# board.net
KiCad netlist of a schematic drawn in EAGLE
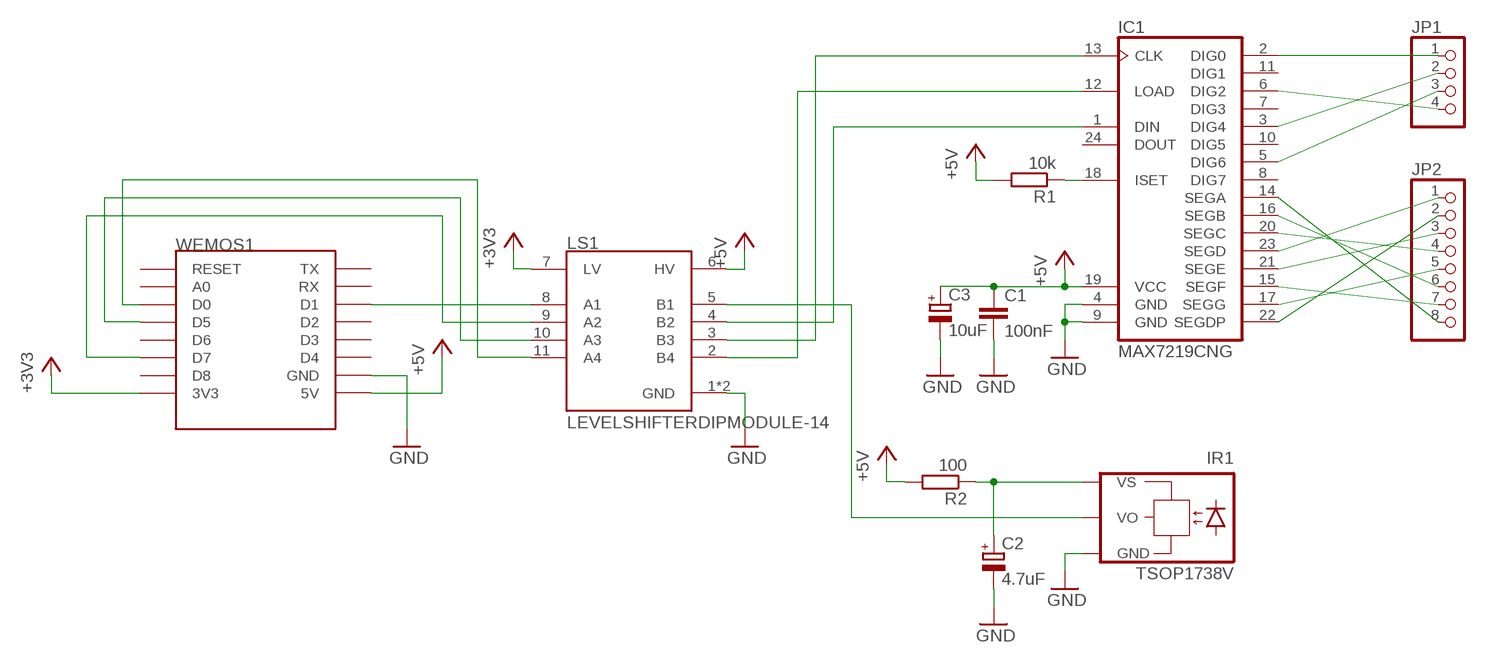
[diagram p0: schematic, sheet 1]

(export (version "E")
  (design (tool "Eeschema 10.0.6"))
  (components
    (comp (ref "C1")
      (value "100nF")
      (footprint "eagle-import:C050-024X044")
      (libsource (lib "eagle-import") (part "C-EU050-024X044"))
    )
    (comp (ref "C2")
      (value "4.7uF")
      (footprint "eagle-import:E1,8-4")
      (libsource (lib "eagle-import") (part "CPOL-EUE1.8-4"))
    )
    (comp (ref "C3")
      (value "10uF")
      (footprint "eagle-import:E1,8-4")
      (libsource (lib "eagle-import") (part "CPOL-EUE1.8-4"))
    )
    (comp (ref "IC1")
      (value "MAX7219CNG")
      (footprint "eagle-import:DIL24-3")
      (fields (field (name "MF") "MAXIM"))
      (libsource (lib "eagle-import") (part "MAX7219CNG"))
    )
    (comp (ref "IR1")
      (value "TSOP1738V")
      (footprint "eagle-import:TSOP17_V")
      (libsource (lib "eagle-import") (part "TSOP17V38"))
    )
    (comp (ref "JP1")
      (value "PINHD-1X4")
      (footprint "eagle-import:1X04")
      (libsource (lib "eagle-import") (part "PINHD-1X4"))
    )
    (comp (ref "JP2")
      (value "PINHD-1X8")
      (footprint "eagle-import:1X08")
      (libsource (lib "eagle-import") (part "PINHD-1X8"))
    )
    (comp (ref "LS1")
      (value "LEVELSHIFTERDIPMODULE-14")
      (footprint "eagle-import:DIP1016W53P254L1969H508Q12B")
      (libsource (lib "eagle-import") (part "LEVELSHIFTERDIPMODULE-14"))
    )
    (comp (ref "R1")
      (value "10k")
      (footprint "eagle-import:0207_10")
      (libsource (lib "eagle-import") (part "R-EU_0207/10"))
    )
    (comp (ref "R2")
      (value "100")
      (footprint "eagle-import:0207_10")
      (libsource (lib "eagle-import") (part "R-EU_0207/10"))
    )
    (comp (ref "WEMOS1")
      (value "WEMOS-D1-MINI")
      (footprint "eagle-import:WEMOS-D1-MINI")
      (libsource (lib "eagle-import") (part "WEMOS-D1-MINI"))
    )
  )
  (nets
    (net (code "1") (name "+3V3") (class "Default")
      (node (ref "LS1") (pin "7") (pinfunction "LV_7") (pintype "power_in"))
      (node (ref "WEMOS1") (pin "3V3") (pinfunction "3V3_3V3") (pintype "bidirectional"))
    )
    (net (code "2") (name "+5V") (class "Default")
      (node (ref "C1") (pin "1") (pinfunction "1_1") (pintype "passive"))
      (node (ref "C3") (pin "+") (pinfunction "+_+") (pintype "passive"))
      (node (ref "IC1") (pin "19") (pinfunction "VCC_19") (pintype "power_in"))
      (node (ref "LS1") (pin "6") (pinfunction "HV_6") (pintype "power_in"))
      (node (ref "R1") (pin "2") (pinfunction "2_2") (pintype "passive"))
      (node (ref "R2") (pin "2") (pinfunction "2_2") (pintype "passive"))
      (node (ref "WEMOS1") (pin "5V") (pinfunction "5V_5V") (pintype "bidirectional"))
    )
    (net (code "3") (name "GND") (class "Default")
      (node (ref "C1") (pin "2") (pinfunction "2_2") (pintype "passive"))
      (node (ref "C2") (pin "-") (pinfunction "-_-") (pintype "passive"))
      (node (ref "C3") (pin "-") (pinfunction "-_-") (pintype "passive"))
      (node (ref "IC1") (pin "4") (pinfunction "GND_4") (pintype "power_in"))
      (node (ref "IC1") (pin "9") (pinfunction "GND_9") (pintype "power_in"))
      (node (ref "IR1") (pin "GND") (pinfunction "GND_GND") (pintype "power_in"))
      (node (ref "LS1") (pin "1") (pinfunction "GND_1") (pintype "power_in"))
      (node (ref "LS1") (pin "12") (pinfunction "GND_12") (pintype "power_in"))
      (node (ref "WEMOS1") (pin "GND") (pinfunction "GND_GND") (pintype "bidirectional"))
    )
    (net (code "4") (name "Net-(C2-Pad+)") (class "Default")
      (node (ref "C2") (pin "+") (pinfunction "+_+") (pintype "passive"))
      (node (ref "IR1") (pin "VS") (pinfunction "VS_VS") (pintype "power_in"))
      (node (ref "R2") (pin "1") (pinfunction "1_1") (pintype "passive"))
    )
    (net (code "5") (name "Net-(IC1-CLK)") (class "Default")
      (node (ref "IC1") (pin "13") (pinfunction "CLK_13") (pintype "input"))
      (node (ref "LS1") (pin "3") (pinfunction "B3_3") (pintype "bidirectional"))
    )
    (net (code "6") (name "Net-(IC1-DIG0)") (class "Default")
      (node (ref "IC1") (pin "2") (pinfunction "DIG0_2") (pintype "output"))
      (node (ref "JP1") (pin "1") (pinfunction "1_1") (pintype "passive"))
    )
    (net (code "7") (name "Net-(IC1-DIG2)") (class "Default")
      (node (ref "IC1") (pin "6") (pinfunction "DIG2_6") (pintype "output"))
      (node (ref "JP1") (pin "4") (pinfunction "4_4") (pintype "passive"))
    )
    (net (code "8") (name "Net-(IC1-DIG4)") (class "Default")
      (node (ref "IC1") (pin "3") (pinfunction "DIG4_3") (pintype "output"))
      (node (ref "JP1") (pin "2") (pinfunction "2_2") (pintype "passive"))
    )
    (net (code "9") (name "Net-(IC1-DIG6)") (class "Default")
      (node (ref "IC1") (pin "5") (pinfunction "DIG6_5") (pintype "output"))
      (node (ref "JP1") (pin "3") (pinfunction "3_3") (pintype "passive"))
    )
    (net (code "10") (name "Net-(IC1-DIN)") (class "Default")
      (node (ref "IC1") (pin "1") (pinfunction "DIN_1") (pintype "input"))
      (node (ref "LS1") (pin "4") (pinfunction "B2_4") (pintype "bidirectional"))
    )
    (net (code "11") (name "Net-(IC1-ISET)") (class "Default")
      (node (ref "IC1") (pin "18") (pinfunction "ISET_18") (pintype "input"))
      (node (ref "R1") (pin "1") (pinfunction "1_1") (pintype "passive"))
    )
    (net (code "12") (name "Net-(IC1-LOAD)") (class "Default")
      (node (ref "IC1") (pin "12") (pinfunction "LOAD_12") (pintype "input"))
      (node (ref "LS1") (pin "2") (pinfunction "B4_2") (pintype "bidirectional"))
    )
    (net (code "13") (name "Net-(IC1-SEGA)") (class "Default")
      (node (ref "IC1") (pin "14") (pinfunction "SEGA_14") (pintype "output"))
      (node (ref "JP2") (pin "8") (pinfunction "8_8") (pintype "passive"))
    )
    (net (code "14") (name "Net-(IC1-SEGB)") (class "Default")
      (node (ref "IC1") (pin "16") (pinfunction "SEGB_16") (pintype "output"))
      (node (ref "JP2") (pin "6") (pinfunction "6_6") (pintype "passive"))
    )
    (net (code "15") (name "Net-(IC1-SEGC)") (class "Default")
      (node (ref "IC1") (pin "20") (pinfunction "SEGC_20") (pintype "output"))
      (node (ref "JP2") (pin "4") (pinfunction "4_4") (pintype "passive"))
    )
    (net (code "16") (name "Net-(IC1-SEGD)") (class "Default")
      (node (ref "IC1") (pin "23") (pinfunction "SEGD_23") (pintype "output"))
      (node (ref "JP2") (pin "1") (pinfunction "1_1") (pintype "passive"))
    )
    (net (code "17") (name "Net-(IC1-SEGDP)") (class "Default")
      (node (ref "IC1") (pin "22") (pinfunction "SEGDP_22") (pintype "output"))
      (node (ref "JP2") (pin "2") (pinfunction "2_2") (pintype "passive"))
    )
    (net (code "18") (name "Net-(IC1-SEGE)") (class "Default")
      (node (ref "IC1") (pin "21") (pinfunction "SEGE_21") (pintype "output"))
      (node (ref "JP2") (pin "3") (pinfunction "3_3") (pintype "passive"))
    )
    (net (code "19") (name "Net-(IC1-SEGF)") (class "Default")
      (node (ref "IC1") (pin "15") (pinfunction "SEGF_15") (pintype "output"))
      (node (ref "JP2") (pin "7") (pinfunction "7_7") (pintype "passive"))
    )
    (net (code "20") (name "Net-(IC1-SEGG)") (class "Default")
      (node (ref "IC1") (pin "17") (pinfunction "SEGG_17") (pintype "output"))
      (node (ref "JP2") (pin "5") (pinfunction "5_5") (pintype "passive"))
    )
    (net (code "21") (name "Net-(LS1-A1)") (class "Default")
      (node (ref "LS1") (pin "8") (pinfunction "A1_8") (pintype "bidirectional"))
      (node (ref "WEMOS1") (pin "D1") (pinfunction "D1_D1") (pintype "bidirectional"))
    )
    (net (code "22") (name "Net-(LS1-A2)") (class "Default")
      (node (ref "LS1") (pin "9") (pinfunction "A2_9") (pintype "bidirectional"))
      (node (ref "WEMOS1") (pin "D7") (pinfunction "D7_D7") (pintype "bidirectional"))
    )
    (net (code "23") (name "Net-(LS1-A3)") (class "Default")
      (node (ref "LS1") (pin "10") (pinfunction "A3_10") (pintype "bidirectional"))
      (node (ref "WEMOS1") (pin "D5") (pinfunction "D5_D5") (pintype "bidirectional"))
    )
    (net (code "24") (name "Net-(LS1-A4)") (class "Default")
      (node (ref "LS1") (pin "11") (pinfunction "A4_11") (pintype "bidirectional"))
      (node (ref "WEMOS1") (pin "D0") (pinfunction "D0_D0") (pintype "bidirectional"))
    )
    (net (code "25") (name "Net-(LS1-B1)") (class "Default")
      (node (ref "IR1") (pin "VO") (pinfunction "VO_VO") (pintype "open_collector"))
      (node (ref "LS1") (pin "5") (pinfunction "B1_5") (pintype "bidirectional"))
    )
    (net (code "26") (name "unconnected-(IC1-DIG1-Pad11)") (class "Default")
      (node (ref "IC1") (pin "11") (pinfunction "DIG1_11") (pintype "output"))
    )
    (net (code "27") (name "unconnected-(IC1-DIG3-Pad7)") (class "Default")
      (node (ref "IC1") (pin "7") (pinfunction "DIG3_7") (pintype "output"))
    )
    (net (code "28") (name "unconnected-(IC1-DIG5-Pad10)") (class "Default")
      (node (ref "IC1") (pin "10") (pinfunction "DIG5_10") (pintype "output"))
    )
    (net (code "29") (name "unconnected-(IC1-DIG7-Pad8)") (class "Default")
      (node (ref "IC1") (pin "8") (pinfunction "DIG7_8") (pintype "output"))
    )
    (net (code "30") (name "unconnected-(IC1-DOUT-Pad24)") (class "Default")
      (node (ref "IC1") (pin "24") (pinfunction "DOUT_24") (pintype "output"))
    )
    (net (code "31") (name "unconnected-(WEMOS1-PadA0)") (class "Default")
      (node (ref "WEMOS1") (pin "A0") (pinfunction "A0_A0") (pintype "bidirectional"))
    )
    (net (code "32") (name "unconnected-(WEMOS1-PadD2)") (class "Default")
      (node (ref "WEMOS1") (pin "D2") (pinfunction "D2_D2") (pintype "bidirectional"))
    )
    (net (code "33") (name "unconnected-(WEMOS1-PadD3)") (class "Default")
      (node (ref "WEMOS1") (pin "D3") (pinfunction "D3_D3") (pintype "bidirectional"))
    )
    (net (code "34") (name "unconnected-(WEMOS1-PadD4)") (class "Default")
      (node (ref "WEMOS1") (pin "D4") (pinfunction "D4_D4") (pintype "bidirectional"))
    )
    (net (code "35") (name "unconnected-(WEMOS1-PadD6)") (class "Default")
      (node (ref "WEMOS1") (pin "D6") (pinfunction "D6_D6") (pintype "bidirectional"))
    )
    (net (code "36") (name "unconnected-(WEMOS1-PadD8)") (class "Default")
      (node (ref "WEMOS1") (pin "D8") (pinfunction "D8_D8") (pintype "bidirectional"))
    )
    (net (code "37") (name "unconnected-(WEMOS1-PadRESET)") (class "Default")
      (node (ref "WEMOS1") (pin "RESET") (pinfunction "RESET_RESET") (pintype "bidirectional"))
    )
    (net (code "38") (name "unconnected-(WEMOS1-PadRX)") (class "Default")
      (node (ref "WEMOS1") (pin "RX") (pinfunction "RX_RX") (pintype "bidirectional"))
    )
    (net (code "39") (name "unconnected-(WEMOS1-PadTX)") (class "Default")
      (node (ref "WEMOS1") (pin "TX") (pinfunction "TX_TX") (pintype "bidirectional"))
    )
  )
)
